# Final_Schematic.net
KiCad netlist of a schematic drawn in EAGLE
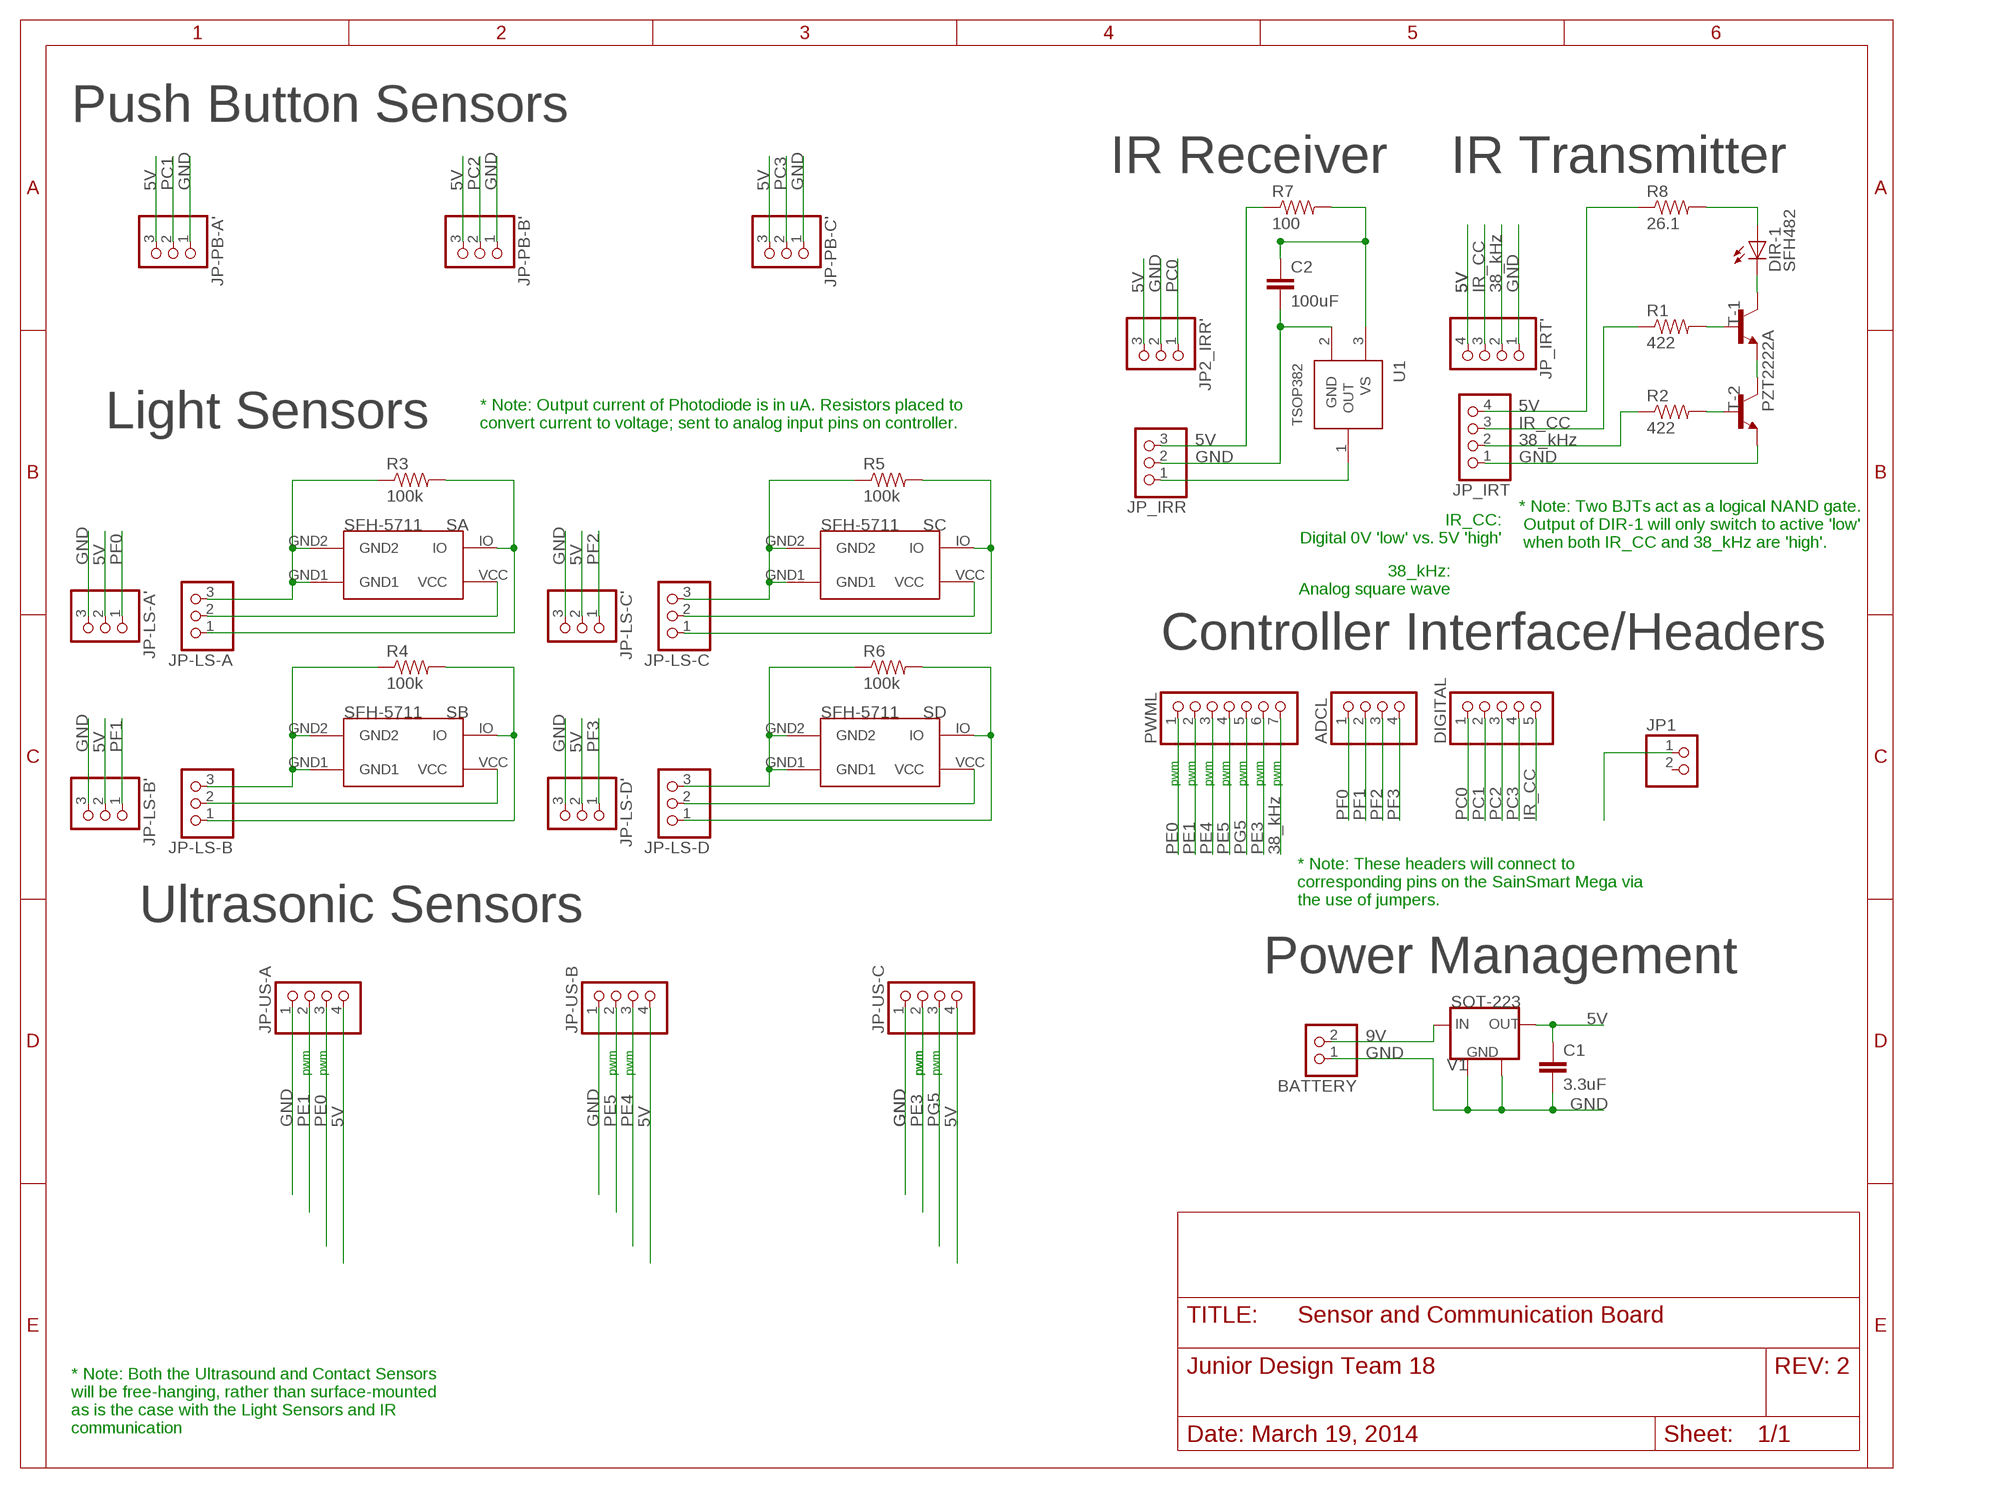
[diagram p0: schematic, sheet 1]

(export (version "E")
  (design (tool "Eeschema 10.0.6"))
  (components
    (comp (ref "ADCL")
      (value "PINHD-1X4")
      (footprint "eagle-import:1X04")
      (libsource (lib "eagle-import") (part "PINHD-1X4"))
    )
    (comp (ref "BATTERY")
      (value "PINHD-1X2")
      (footprint "eagle-import:1X02")
      (libsource (lib "eagle-import") (part "PINHD-1X2"))
    )
    (comp (ref "C1")
      (value "3.3uF")
      (footprint "eagle-import:0603-CAP")
      (libsource (lib "eagle-import") (part "CAP0603-CAP"))
    )
    (comp (ref "C2")
      (value "100uF")
      (footprint "eagle-import:1206")
      (libsource (lib "eagle-import") (part "CAP1206"))
    )
    (comp (ref "DIGITAL")
      (value "PINHD-1X5")
      (footprint "eagle-import:1X05")
      (libsource (lib "eagle-import") (part "PINHD-1X5"))
    )
    (comp (ref "DIR-1")
      (value "SFH482")
      (footprint "eagle-import:SFH482")
      (libsource (lib "eagle-import") (part "SFH482"))
    )
    (comp (ref "JP-LS-A")
      (value "PINHD-1X3")
      (footprint "eagle-import:1X03")
      (libsource (lib "eagle-import") (part "PINHD-1X3"))
    )
    (comp (ref "JP-LS-A'")
      (value "PINHD-1X3")
      (footprint "eagle-import:1X03")
      (libsource (lib "eagle-import") (part "PINHD-1X3"))
    )
    (comp (ref "JP-LS-B")
      (value "PINHD-1X3")
      (footprint "eagle-import:1X03")
      (libsource (lib "eagle-import") (part "PINHD-1X3"))
    )
    (comp (ref "JP-LS-B'")
      (value "PINHD-1X3")
      (footprint "eagle-import:1X03")
      (libsource (lib "eagle-import") (part "PINHD-1X3"))
    )
    (comp (ref "JP-LS-C")
      (value "PINHD-1X3")
      (footprint "eagle-import:1X03")
      (libsource (lib "eagle-import") (part "PINHD-1X3"))
    )
    (comp (ref "JP-LS-C'")
      (value "PINHD-1X3")
      (footprint "eagle-import:1X03")
      (libsource (lib "eagle-import") (part "PINHD-1X3"))
    )
    (comp (ref "JP-LS-D")
      (value "PINHD-1X3")
      (footprint "eagle-import:1X03")
      (libsource (lib "eagle-import") (part "PINHD-1X3"))
    )
    (comp (ref "JP-LS-D'")
      (value "PINHD-1X3")
      (footprint "eagle-import:1X03")
      (libsource (lib "eagle-import") (part "PINHD-1X3"))
    )
    (comp (ref "JP-PB-A'")
      (value "PINHD-1X3")
      (footprint "eagle-import:1X03")
      (libsource (lib "eagle-import") (part "PINHD-1X3"))
    )
    (comp (ref "JP-PB-B'")
      (value "PINHD-1X3")
      (footprint "eagle-import:1X03")
      (libsource (lib "eagle-import") (part "PINHD-1X3"))
    )
    (comp (ref "JP-PB-C'")
      (value "PINHD-1X3")
      (footprint "eagle-import:1X03")
      (libsource (lib "eagle-import") (part "PINHD-1X3"))
    )
    (comp (ref "JP-US-A")
      (value "PINHD-1X4")
      (footprint "eagle-import:1X04")
      (libsource (lib "eagle-import") (part "PINHD-1X4"))
    )
    (comp (ref "JP-US-B")
      (value "PINHD-1X4")
      (footprint "eagle-import:1X04")
      (libsource (lib "eagle-import") (part "PINHD-1X4"))
    )
    (comp (ref "JP-US-C")
      (value "PINHD-1X4")
      (footprint "eagle-import:1X04")
      (libsource (lib "eagle-import") (part "PINHD-1X4"))
    )
    (comp (ref "JP1")
      (value "PINHD-1X2")
      (footprint "eagle-import:1X02")
      (libsource (lib "eagle-import") (part "PINHD-1X2"))
    )
    (comp (ref "JP2_IRR'")
      (value "PINHD-1X3")
      (footprint "eagle-import:1X03")
      (libsource (lib "eagle-import") (part "PINHD-1X3"))
    )
    (comp (ref "JP_IRR")
      (value "PINHD-1X3")
      (footprint "eagle-import:1X03")
      (libsource (lib "eagle-import") (part "PINHD-1X3"))
    )
    (comp (ref "JP_IRT")
      (value "PINHD-1X4")
      (footprint "eagle-import:1X04")
      (libsource (lib "eagle-import") (part "PINHD-1X4"))
    )
    (comp (ref "JP_IRT'")
      (value "PINHD-1X4")
      (footprint "eagle-import:1X04")
      (libsource (lib "eagle-import") (part "PINHD-1X4"))
    )
    (comp (ref "PWML")
      (value "PINHD-1X7")
      (footprint "eagle-import:1X07")
      (libsource (lib "eagle-import") (part "PINHD-1X7"))
    )
    (comp (ref "R1")
      (value "422")
      (footprint "eagle-import:R2512")
      (libsource (lib "eagle-import") (part "RESISTOR2512"))
    )
    (comp (ref "R2")
      (value "422")
      (footprint "eagle-import:R2512")
      (libsource (lib "eagle-import") (part "RESISTOR2512"))
    )
    (comp (ref "R3")
      (value "100k")
      (footprint "eagle-import:0805")
      (libsource (lib "eagle-import") (part "RESISTOR0805-RES"))
    )
    (comp (ref "R4")
      (value "100k")
      (footprint "eagle-import:0805")
      (libsource (lib "eagle-import") (part "RESISTOR0805-RES"))
    )
    (comp (ref "R5")
      (value "100k")
      (footprint "eagle-import:0805")
      (libsource (lib "eagle-import") (part "RESISTOR0805-RES"))
    )
    (comp (ref "R6")
      (value "100k")
      (footprint "eagle-import:0805")
      (libsource (lib "eagle-import") (part "RESISTOR0805-RES"))
    )
    (comp (ref "R7")
      (value "100")
      (footprint "eagle-import:0805")
      (libsource (lib "eagle-import") (part "RESISTOR0805-RES"))
    )
    (comp (ref "R8")
      (value "26.1")
      (footprint "eagle-import:R2512")
      (libsource (lib "eagle-import") (part "RESISTOR2512"))
    )
    (comp (ref "SFH-5711-A")
      (value "SA")
      (footprint "eagle-import:DIODE")
      (libsource (lib "eagle-import") (part "SFH5711"))
    )
    (comp (ref "SFH-5711-B")
      (value "SB")
      (footprint "eagle-import:DIODE")
      (libsource (lib "eagle-import") (part "SFH5711"))
    )
    (comp (ref "SFH-5711-C")
      (value "SC")
      (footprint "eagle-import:DIODE")
      (libsource (lib "eagle-import") (part "SFH5711"))
    )
    (comp (ref "SFH-5711-D")
      (value "SD")
      (footprint "eagle-import:DIODE")
      (libsource (lib "eagle-import") (part "SFH5711"))
    )
    (comp (ref "SOT-223")
      (value "V1")
      (footprint "eagle-import:SOT223")
      (libsource (lib "eagle-import") (part "V_REG_LM1117SOT223"))
    )
    (comp (ref "T-1")
      (value "PZT2222A")
      (footprint "eagle-import:SOT223")
      (libsource (lib "eagle-import") (part "PZT2222A"))
    )
    (comp (ref "T-2")
      (value "PZT2222A")
      (footprint "eagle-import:SOT223")
      (libsource (lib "eagle-import") (part "PZT2222A"))
    )
    (comp (ref "U1")
      (value "TSOP382")
      (footprint "eagle-import:TSOP382")
      (libsource (lib "eagle-import") (part "TSOP382"))
    )
  )
  (nets
    (net (code "1") (name "/5V") (class "Default")
      (node (ref "C1") (pin "1") (pinfunction "1_1") (pintype "passive"))
      (node (ref "JP-LS-A'") (pin "2") (pinfunction "2_2") (pintype "passive"))
      (node (ref "JP-LS-B'") (pin "2") (pinfunction "2_2") (pintype "passive"))
      (node (ref "JP-LS-C'") (pin "2") (pinfunction "2_2") (pintype "passive"))
      (node (ref "JP-LS-D'") (pin "2") (pinfunction "2_2") (pintype "passive"))
      (node (ref "JP-PB-A'") (pin "3") (pinfunction "3_3") (pintype "passive"))
      (node (ref "JP-PB-B'") (pin "3") (pinfunction "3_3") (pintype "passive"))
      (node (ref "JP-PB-C'") (pin "3") (pinfunction "3_3") (pintype "passive"))
      (node (ref "JP-US-A") (pin "4") (pinfunction "4_4") (pintype "passive"))
      (node (ref "JP-US-B") (pin "4") (pinfunction "4_4") (pintype "passive"))
      (node (ref "JP-US-C") (pin "4") (pinfunction "4_4") (pintype "passive"))
      (node (ref "JP2_IRR'") (pin "3") (pinfunction "3_3") (pintype "passive"))
      (node (ref "JP_IRT'") (pin "4") (pinfunction "4_4") (pintype "passive"))
      (node (ref "SOT-223") (pin "GND1") (pinfunction "OUT_GND1") (pintype "output"))
    )
    (net (code "2") (name "/GND") (class "Default")
      (node (ref "BATTERY") (pin "1") (pinfunction "1_1") (pintype "passive"))
      (node (ref "C1") (pin "2") (pinfunction "2_2") (pintype "passive"))
      (node (ref "JP-LS-A'") (pin "3") (pinfunction "3_3") (pintype "passive"))
      (node (ref "JP-LS-B'") (pin "3") (pinfunction "3_3") (pintype "passive"))
      (node (ref "JP-LS-C'") (pin "3") (pinfunction "3_3") (pintype "passive"))
      (node (ref "JP-LS-D'") (pin "3") (pinfunction "3_3") (pintype "passive"))
      (node (ref "JP-PB-A'") (pin "1") (pinfunction "1_1") (pintype "passive"))
      (node (ref "JP-PB-B'") (pin "1") (pinfunction "1_1") (pintype "passive"))
      (node (ref "JP-PB-C'") (pin "1") (pinfunction "1_1") (pintype "passive"))
      (node (ref "JP-US-A") (pin "1") (pinfunction "1_1") (pintype "passive"))
      (node (ref "JP-US-B") (pin "1") (pinfunction "1_1") (pintype "passive"))
      (node (ref "JP-US-C") (pin "1") (pinfunction "1_1") (pintype "passive"))
      (node (ref "JP1") (pin "1") (pinfunction "1_1") (pintype "passive"))
      (node (ref "JP2_IRR'") (pin "2") (pinfunction "2_2") (pintype "passive"))
      (node (ref "JP_IRT'") (pin "1") (pinfunction "1_1") (pintype "passive"))
      (node (ref "SOT-223") (pin "GND2") (pinfunction "GND1_GND2") (pintype "output"))
      (node (ref "SOT-223") (pin "IN") (pinfunction "GND2_IN") (pintype "input"))
    )
    (net (code "3") (name "/IR_CC") (class "Default")
      (node (ref "DIGITAL") (pin "5") (pinfunction "5_5") (pintype "passive"))
      (node (ref "JP_IRT'") (pin "3") (pinfunction "3_3") (pintype "passive"))
    )
    (net (code "4") (name "/N$7") (class "Default")
      (node (ref "JP_IRT'") (pin "2") (pinfunction "2_2") (pintype "passive"))
      (node (ref "PWML") (pin "7") (pinfunction "7_7") (pintype "passive"))
    )
    (net (code "5") (name "/PC0") (class "Default")
      (node (ref "DIGITAL") (pin "1") (pinfunction "1_1") (pintype "passive"))
      (node (ref "JP2_IRR'") (pin "1") (pinfunction "1_1") (pintype "passive"))
    )
    (net (code "6") (name "/PC1") (class "Default")
      (node (ref "DIGITAL") (pin "2") (pinfunction "2_2") (pintype "passive"))
      (node (ref "JP-PB-A'") (pin "2") (pinfunction "2_2") (pintype "passive"))
    )
    (net (code "7") (name "/PC2") (class "Default")
      (node (ref "DIGITAL") (pin "3") (pinfunction "3_3") (pintype "passive"))
      (node (ref "JP-PB-B'") (pin "2") (pinfunction "2_2") (pintype "passive"))
    )
    (net (code "8") (name "/PC3") (class "Default")
      (node (ref "DIGITAL") (pin "4") (pinfunction "4_4") (pintype "passive"))
      (node (ref "JP-PB-C'") (pin "2") (pinfunction "2_2") (pintype "passive"))
    )
    (net (code "9") (name "/PE0") (class "Default")
      (node (ref "JP-US-A") (pin "3") (pinfunction "3_3") (pintype "passive"))
      (node (ref "PWML") (pin "1") (pinfunction "1_1") (pintype "passive"))
    )
    (net (code "10") (name "/PE1") (class "Default")
      (node (ref "JP-US-A") (pin "2") (pinfunction "2_2") (pintype "passive"))
      (node (ref "PWML") (pin "2") (pinfunction "2_2") (pintype "passive"))
    )
    (net (code "11") (name "/PE3") (class "Default")
      (node (ref "JP-US-C") (pin "2") (pinfunction "2_2") (pintype "passive"))
      (node (ref "PWML") (pin "6") (pinfunction "6_6") (pintype "passive"))
    )
    (net (code "12") (name "/PE4") (class "Default")
      (node (ref "JP-US-B") (pin "3") (pinfunction "3_3") (pintype "passive"))
      (node (ref "PWML") (pin "3") (pinfunction "3_3") (pintype "passive"))
    )
    (net (code "13") (name "/PE5") (class "Default")
      (node (ref "JP-US-B") (pin "2") (pinfunction "2_2") (pintype "passive"))
      (node (ref "PWML") (pin "4") (pinfunction "4_4") (pintype "passive"))
    )
    (net (code "14") (name "/PF0") (class "Default")
      (node (ref "ADCL") (pin "1") (pinfunction "1_1") (pintype "passive"))
      (node (ref "JP-LS-A'") (pin "1") (pinfunction "1_1") (pintype "passive"))
    )
    (net (code "15") (name "/PF1") (class "Default")
      (node (ref "ADCL") (pin "2") (pinfunction "2_2") (pintype "passive"))
      (node (ref "JP-LS-B'") (pin "1") (pinfunction "1_1") (pintype "passive"))
    )
    (net (code "16") (name "/PF2") (class "Default")
      (node (ref "ADCL") (pin "3") (pinfunction "3_3") (pintype "passive"))
      (node (ref "JP-LS-C'") (pin "1") (pinfunction "1_1") (pintype "passive"))
    )
    (net (code "17") (name "/PF3") (class "Default")
      (node (ref "ADCL") (pin "4") (pinfunction "4_4") (pintype "passive"))
      (node (ref "JP-LS-D'") (pin "1") (pinfunction "1_1") (pintype "passive"))
    )
    (net (code "18") (name "/PG5") (class "Default")
      (node (ref "JP-US-C") (pin "3") (pinfunction "3_3") (pintype "passive"))
      (node (ref "PWML") (pin "5") (pinfunction "5_5") (pintype "passive"))
    )
    (net (code "19") (name "Net-(DIR-1-C)") (class "Default")
      (node (ref "DIR-1") (pin "K") (pinfunction "C_K") (pintype "passive"))
      (node (ref "T-1") (pin "2") (pinfunction "C_2") (pintype "passive"))
      (node (ref "T-1") (pin "4") (pinfunction "C_4") (pintype "passive"))
    )
    (net (code "20") (name "Net-(DIR-1-PadA)") (class "Default")
      (node (ref "DIR-1") (pin "A") (pinfunction "A_A") (pintype "passive"))
      (node (ref "R8") (pin "2") (pinfunction "2_2") (pintype "passive"))
    )
    (net (code "21") (name "Net-(JP-LS-A-Pad1)") (class "Default")
      (node (ref "JP-LS-A") (pin "1") (pinfunction "1_1") (pintype "passive"))
      (node (ref "R3") (pin "2") (pinfunction "2_2") (pintype "passive"))
      (node (ref "SFH-5711-A") (pin "IO") (pinfunction "IO_IO") (pintype "bidirectional"))
    )
    (net (code "22") (name "Net-(JP-LS-A-Pad2)") (class "Default")
      (node (ref "JP-LS-A") (pin "2") (pinfunction "2_2") (pintype "passive"))
      (node (ref "SFH-5711-A") (pin "VCC") (pinfunction "VCC_VCC") (pintype "bidirectional"))
    )
    (net (code "23") (name "Net-(JP-LS-A-Pad3)") (class "Default")
      (node (ref "JP-LS-A") (pin "3") (pinfunction "3_3") (pintype "passive"))
      (node (ref "R3") (pin "1") (pinfunction "1_1") (pintype "passive"))
      (node (ref "SFH-5711-A") (pin "GND1") (pinfunction "GND1_GND1") (pintype "bidirectional"))
      (node (ref "SFH-5711-A") (pin "GND2") (pinfunction "GND2_GND2") (pintype "bidirectional"))
    )
    (net (code "24") (name "Net-(JP-LS-B-Pad1)") (class "Default")
      (node (ref "JP-LS-B") (pin "1") (pinfunction "1_1") (pintype "passive"))
      (node (ref "R4") (pin "2") (pinfunction "2_2") (pintype "passive"))
      (node (ref "SFH-5711-B") (pin "IO") (pinfunction "IO_IO") (pintype "bidirectional"))
    )
    (net (code "25") (name "Net-(JP-LS-B-Pad2)") (class "Default")
      (node (ref "JP-LS-B") (pin "2") (pinfunction "2_2") (pintype "passive"))
      (node (ref "SFH-5711-B") (pin "VCC") (pinfunction "VCC_VCC") (pintype "bidirectional"))
    )
    (net (code "26") (name "Net-(JP-LS-B-Pad3)") (class "Default")
      (node (ref "JP-LS-B") (pin "3") (pinfunction "3_3") (pintype "passive"))
      (node (ref "R4") (pin "1") (pinfunction "1_1") (pintype "passive"))
      (node (ref "SFH-5711-B") (pin "GND1") (pinfunction "GND1_GND1") (pintype "bidirectional"))
      (node (ref "SFH-5711-B") (pin "GND2") (pinfunction "GND2_GND2") (pintype "bidirectional"))
    )
    (net (code "27") (name "Net-(JP-LS-C-Pad1)") (class "Default")
      (node (ref "JP-LS-C") (pin "1") (pinfunction "1_1") (pintype "passive"))
      (node (ref "R5") (pin "2") (pinfunction "2_2") (pintype "passive"))
      (node (ref "SFH-5711-C") (pin "IO") (pinfunction "IO_IO") (pintype "bidirectional"))
    )
    (net (code "28") (name "Net-(JP-LS-C-Pad2)") (class "Default")
      (node (ref "JP-LS-C") (pin "2") (pinfunction "2_2") (pintype "passive"))
      (node (ref "SFH-5711-C") (pin "VCC") (pinfunction "VCC_VCC") (pintype "bidirectional"))
    )
    (net (code "29") (name "Net-(JP-LS-C-Pad3)") (class "Default")
      (node (ref "JP-LS-C") (pin "3") (pinfunction "3_3") (pintype "passive"))
      (node (ref "R5") (pin "1") (pinfunction "1_1") (pintype "passive"))
      (node (ref "SFH-5711-C") (pin "GND1") (pinfunction "GND1_GND1") (pintype "bidirectional"))
      (node (ref "SFH-5711-C") (pin "GND2") (pinfunction "GND2_GND2") (pintype "bidirectional"))
    )
    (net (code "30") (name "Net-(JP-LS-D-Pad1)") (class "Default")
      (node (ref "JP-LS-D") (pin "1") (pinfunction "1_1") (pintype "passive"))
      (node (ref "R6") (pin "2") (pinfunction "2_2") (pintype "passive"))
      (node (ref "SFH-5711-D") (pin "IO") (pinfunction "IO_IO") (pintype "bidirectional"))
    )
    (net (code "31") (name "Net-(JP-LS-D-Pad2)") (class "Default")
      (node (ref "JP-LS-D") (pin "2") (pinfunction "2_2") (pintype "passive"))
      (node (ref "SFH-5711-D") (pin "VCC") (pinfunction "VCC_VCC") (pintype "bidirectional"))
    )
    (net (code "32") (name "Net-(JP-LS-D-Pad3)") (class "Default")
      (node (ref "JP-LS-D") (pin "3") (pinfunction "3_3") (pintype "passive"))
      (node (ref "R6") (pin "1") (pinfunction "1_1") (pintype "passive"))
      (node (ref "SFH-5711-D") (pin "GND1") (pinfunction "GND1_GND1") (pintype "bidirectional"))
      (node (ref "SFH-5711-D") (pin "GND2") (pinfunction "GND2_GND2") (pintype "bidirectional"))
    )
    (net (code "33") (name "Net-(JP_IRR-Pad3)") (class "Default")
      (node (ref "JP_IRR") (pin "3") (pinfunction "3_3") (pintype "passive"))
      (node (ref "R7") (pin "1") (pinfunction "1_1") (pintype "passive"))
    )
    (net (code "34") (name "Net-(JP_IRT-Pad2)") (class "Default")
      (node (ref "JP_IRT") (pin "2") (pinfunction "2_2") (pintype "passive"))
      (node (ref "R2") (pin "1") (pinfunction "1_1") (pintype "passive"))
    )
    (net (code "35") (name "Net-(JP_IRT-Pad3)") (class "Default")
      (node (ref "JP_IRT") (pin "3") (pinfunction "3_3") (pintype "passive"))
      (node (ref "R1") (pin "1") (pinfunction "1_1") (pintype "passive"))
    )
    (net (code "36") (name "Net-(JP_IRT-Pad4)") (class "Default")
      (node (ref "JP_IRT") (pin "4") (pinfunction "4_4") (pintype "passive"))
      (node (ref "R8") (pin "1") (pinfunction "1_1") (pintype "passive"))
    )
    (net (code "37") (name "Net-(SOT-223-IN)") (class "Default")
      (node (ref "BATTERY") (pin "2") (pinfunction "2_2") (pintype "passive"))
      (node (ref "SOT-223") (pin "OUT") (pinfunction "IN_OUT") (pintype "input"))
    )
    (net (code "38") (name "Net-(T-1-B)") (class "Default")
      (node (ref "R1") (pin "2") (pinfunction "2_2") (pintype "passive"))
      (node (ref "T-1") (pin "1") (pinfunction "B_1") (pintype "passive"))
    )
    (net (code "39") (name "Net-(T-1-E)") (class "Default")
      (node (ref "T-1") (pin "3") (pinfunction "E_3") (pintype "passive"))
      (node (ref "T-2") (pin "2") (pinfunction "C_2") (pintype "passive"))
      (node (ref "T-2") (pin "4") (pinfunction "C_4") (pintype "passive"))
    )
    (net (code "40") (name "Net-(T-2-B)") (class "Default")
      (node (ref "R2") (pin "2") (pinfunction "2_2") (pintype "passive"))
      (node (ref "T-2") (pin "1") (pinfunction "B_1") (pintype "passive"))
    )
    (net (code "41") (name "Net-(T-2-E)") (class "Default")
      (node (ref "JP_IRT") (pin "1") (pinfunction "1_1") (pintype "passive"))
      (node (ref "T-2") (pin "3") (pinfunction "E_3") (pintype "passive"))
    )
    (net (code "42") (name "Net-(U1-GND)") (class "Default")
      (node (ref "C2") (pin "2") (pinfunction "2_2") (pintype "passive"))
      (node (ref "JP_IRR") (pin "2") (pinfunction "2_2") (pintype "passive"))
      (node (ref "U1") (pin "2") (pinfunction "GND_2") (pintype "bidirectional"))
    )
    (net (code "43") (name "Net-(U1-OUT)") (class "Default")
      (node (ref "JP_IRR") (pin "1") (pinfunction "1_1") (pintype "passive"))
      (node (ref "U1") (pin "1") (pinfunction "OUT_1") (pintype "bidirectional"))
    )
    (net (code "44") (name "Net-(U1-VS)") (class "Default")
      (node (ref "C2") (pin "1") (pinfunction "1_1") (pintype "passive"))
      (node (ref "R7") (pin "2") (pinfunction "2_2") (pintype "passive"))
      (node (ref "U1") (pin "3") (pinfunction "VS_3") (pintype "bidirectional"))
    )
    (net (code "45") (name "unconnected-(JP1-Pad2)") (class "Default")
      (node (ref "JP1") (pin "2") (pinfunction "2_2") (pintype "passive"))
    )
  )
)
